# E16-PDB-5-LOAD_1.net
KiCad netlist of a schematic drawn in Altium Designer
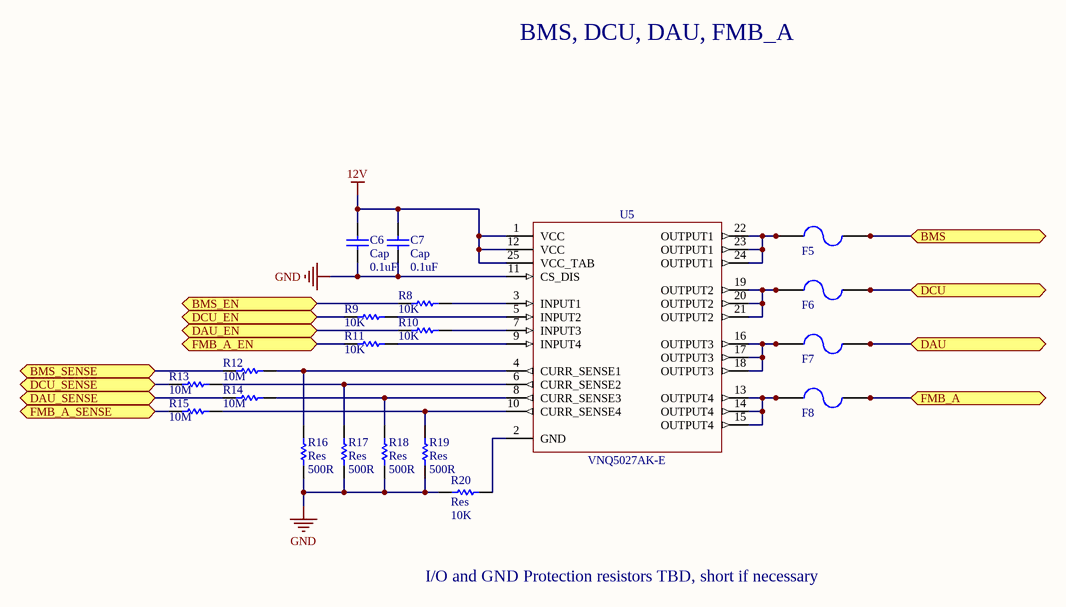
[diagram p0: E16-PDB-5-LOAD_1.SchDoc]

(export (version "E")
  (design (tool "Eeschema 10.0.6"))
  (components
    (comp (ref "C6")
      (value "Cap")
      (footprint "C0805")
      (description "Capacitor")
      (fields (field (name "ALTIUM_VALUE") "0.1uF") (field (name "PUBLISHER") "Altium Limited"))
      (libsource (lib "Capacitors") (part "Cap"))
    )
    (comp (ref "C7")
      (value "Cap")
      (footprint "C0805")
      (description "Capacitor")
      (fields (field (name "ALTIUM_VALUE") "0.1uF") (field (name "PUBLISHER") "Altium Limited"))
      (libsource (lib "Capacitors") (part "Cap"))
    )
    (comp (ref "F5")
      (value "BK-6013")
      (footprint "BK-6013")
      (description "FUSE HOLDER BLADE PCB")
      (libsource (lib "Fuses") (part "BK-6013"))
    )
    (comp (ref "F6")
      (value "BK-6013")
      (footprint "BK-6013")
      (description "FUSE HOLDER BLADE PCB")
      (libsource (lib "Fuses") (part "BK-6013"))
    )
    (comp (ref "F7")
      (value "BK-6013")
      (footprint "BK-6013")
      (description "FUSE HOLDER BLADE PCB")
      (libsource (lib "Fuses") (part "BK-6013"))
    )
    (comp (ref "F8")
      (value "BK-6013")
      (footprint "BK-6013")
      (description "FUSE HOLDER BLADE PCB")
      (libsource (lib "Fuses") (part "BK-6013"))
    )
    (comp (ref "R8")
      (value "10K")
      (footprint "2012[0805]")
      (description "Surface Mount Resistor")
      (fields (field (name "Comment") "Res") (field (name "PUBLISHER") "Altium Limited"))
      (libsource (lib "Resistors") (part "Res"))
    )
    (comp (ref "R9")
      (value "10K")
      (footprint "2012[0805]")
      (description "Surface Mount Resistor")
      (fields (field (name "Comment") "Res") (field (name "PUBLISHER") "Altium Limited"))
      (libsource (lib "Resistors") (part "Res"))
    )
    (comp (ref "R10")
      (value "10K")
      (footprint "2012[0805]")
      (description "Surface Mount Resistor")
      (fields (field (name "Comment") "Res") (field (name "PUBLISHER") "Altium Limited"))
      (libsource (lib "Resistors") (part "Res"))
    )
    (comp (ref "R11")
      (value "10K")
      (footprint "2012[0805]")
      (description "Surface Mount Resistor")
      (fields (field (name "Comment") "Res") (field (name "PUBLISHER") "Altium Limited"))
      (libsource (lib "Resistors") (part "Res"))
    )
    (comp (ref "R12")
      (value "10M")
      (footprint "2012[0805]")
      (description "Surface Mount Resistor")
      (fields (field (name "Comment") "Res") (field (name "PUBLISHER") "Altium Limited"))
      (libsource (lib "Resistors") (part "Res"))
    )
    (comp (ref "R13")
      (value "10M")
      (footprint "2012[0805]")
      (description "Surface Mount Resistor")
      (fields (field (name "Comment") "Res") (field (name "PUBLISHER") "Altium Limited"))
      (libsource (lib "Resistors") (part "Res"))
    )
    (comp (ref "R14")
      (value "10M")
      (footprint "2012[0805]")
      (description "Surface Mount Resistor")
      (fields (field (name "Comment") "Res") (field (name "PUBLISHER") "Altium Limited"))
      (libsource (lib "Resistors") (part "Res"))
    )
    (comp (ref "R15")
      (value "10M")
      (footprint "2012[0805]")
      (description "Surface Mount Resistor")
      (fields (field (name "Comment") "Res") (field (name "PUBLISHER") "Altium Limited"))
      (libsource (lib "Resistors") (part "Res"))
    )
    (comp (ref "R16")
      (value "Res")
      (footprint "2012[0805]")
      (description "Surface Mount Resistor")
      (fields (field (name "ALTIUM_VALUE") "500R") (field (name "PUBLISHER") "Altium Limited"))
      (libsource (lib "Resistors") (part "Res"))
    )
    (comp (ref "R17")
      (value "Res")
      (footprint "2012[0805]")
      (description "Surface Mount Resistor")
      (fields (field (name "ALTIUM_VALUE") "500R") (field (name "PUBLISHER") "Altium Limited"))
      (libsource (lib "Resistors") (part "Res"))
    )
    (comp (ref "R18")
      (value "Res")
      (footprint "2012[0805]")
      (description "Surface Mount Resistor")
      (fields (field (name "ALTIUM_VALUE") "500R") (field (name "PUBLISHER") "Altium Limited"))
      (libsource (lib "Resistors") (part "Res"))
    )
    (comp (ref "R19")
      (value "Res")
      (footprint "2012[0805]")
      (description "Surface Mount Resistor")
      (fields (field (name "ALTIUM_VALUE") "500R") (field (name "PUBLISHER") "Altium Limited"))
      (libsource (lib "Resistors") (part "Res"))
    )
    (comp (ref "R20")
      (value "Res")
      (footprint "2012[0805]")
      (description "Surface Mount Resistor")
      (fields (field (name "ALTIUM_VALUE") "10K") (field (name "PUBLISHER") "Altium Limited"))
      (libsource (lib "Resistors") (part "Res"))
    )
    (comp (ref "U5")
      (value "U_VNQ5027AK-E")
      (footprint "PowerSSO-24")
      (description "LOAD CHANNEL HIGH SIDE 42 A 4 Channel")
      (fields (field (name "MFG") "STmicroelectronics") (field (name "MFG_PN") "VNQ5027AK-E"))
      (libsource (lib "Transistors") (part "U_VNQ5027AK-E"))
    )
  )
  (nets
    (net (code "1") (name "/BMS") (class "Default")
      (node (ref "F5") (pin "3") (pinfunction "3_3") (pintype "passive"))
      (node (ref "F5") (pin "4") (pinfunction "4_4") (pintype "passive"))
    )
    (net (code "2") (name "/BMS_EN") (class "Default")
      (node (ref "R8") (pin "2") (pinfunction "2_2") (pintype "passive"))
    )
    (net (code "3") (name "/BMS_SENSE") (class "Default")
      (node (ref "R12") (pin "2") (pinfunction "2_2") (pintype "passive"))
    )
    (net (code "4") (name "/DAU") (class "Default")
      (node (ref "F7") (pin "3") (pinfunction "3_3") (pintype "passive"))
      (node (ref "F7") (pin "4") (pinfunction "4_4") (pintype "passive"))
    )
    (net (code "5") (name "/DAU_EN") (class "Default")
      (node (ref "R10") (pin "2") (pinfunction "2_2") (pintype "passive"))
    )
    (net (code "6") (name "/DAU_SENSE") (class "Default")
      (node (ref "R14") (pin "2") (pinfunction "2_2") (pintype "passive"))
    )
    (net (code "7") (name "/DCU") (class "Default")
      (node (ref "F6") (pin "3") (pinfunction "3_3") (pintype "passive"))
      (node (ref "F6") (pin "4") (pinfunction "4_4") (pintype "passive"))
    )
    (net (code "8") (name "/DCU_EN") (class "Default")
      (node (ref "R9") (pin "2") (pinfunction "2_2") (pintype "passive"))
    )
    (net (code "9") (name "/DCU_SENSE") (class "Default")
      (node (ref "R13") (pin "2") (pinfunction "2_2") (pintype "passive"))
    )
    (net (code "10") (name "/FMB_A") (class "Default")
      (node (ref "F8") (pin "3") (pinfunction "3_3") (pintype "passive"))
      (node (ref "F8") (pin "4") (pinfunction "4_4") (pintype "passive"))
    )
    (net (code "11") (name "/FMB_A_EN") (class "Default")
      (node (ref "R11") (pin "2") (pinfunction "2_2") (pintype "passive"))
    )
    (net (code "12") (name "/FMB_A_SENSE") (class "Default")
      (node (ref "R15") (pin "2") (pinfunction "2_2") (pintype "passive"))
    )
    (net (code "13") (name "12V") (class "Default")
      (node (ref "C6") (pin "2") (pinfunction "2_2") (pintype "passive"))
      (node (ref "C7") (pin "2") (pinfunction "2_2") (pintype "passive"))
      (node (ref "U5") (pin "1") (pinfunction "VCC_1") (pintype "power_in"))
      (node (ref "U5") (pin "12") (pinfunction "VCC_12") (pintype "power_in"))
      (node (ref "U5") (pin "25") (pinfunction "VCC_TAB_25") (pintype "power_in"))
    )
    (net (code "14") (name "GND") (class "Default")
      (node (ref "C6") (pin "1") (pinfunction "1_1") (pintype "passive"))
      (node (ref "C7") (pin "1") (pinfunction "1_1") (pintype "passive"))
      (node (ref "R16") (pin "1") (pinfunction "1_1") (pintype "passive"))
      (node (ref "R17") (pin "1") (pinfunction "1_1") (pintype "passive"))
      (node (ref "R18") (pin "1") (pinfunction "1_1") (pintype "passive"))
      (node (ref "R19") (pin "1") (pinfunction "1_1") (pintype "passive"))
      (node (ref "R20") (pin "2") (pinfunction "2_2") (pintype "passive"))
      (node (ref "U5") (pin "11") (pinfunction "CS_DIS_11") (pintype "input"))
    )
    (net (code "15") (name "Net-(F5-Pad1)") (class "Default")
      (node (ref "F5") (pin "1") (pinfunction "1_1") (pintype "passive"))
      (node (ref "F5") (pin "2") (pinfunction "2_2") (pintype "passive"))
      (node (ref "U5") (pin "22") (pinfunction "OUTPUT1_22") (pintype "output"))
      (node (ref "U5") (pin "23") (pinfunction "OUTPUT1_23") (pintype "output"))
      (node (ref "U5") (pin "24") (pinfunction "OUTPUT1_24") (pintype "output"))
    )
    (net (code "16") (name "Net-(F6-Pad1)") (class "Default")
      (node (ref "F6") (pin "1") (pinfunction "1_1") (pintype "passive"))
      (node (ref "F6") (pin "2") (pinfunction "2_2") (pintype "passive"))
      (node (ref "U5") (pin "19") (pinfunction "OUTPUT2_19") (pintype "output"))
      (node (ref "U5") (pin "20") (pinfunction "OUTPUT2_20") (pintype "output"))
      (node (ref "U5") (pin "21") (pinfunction "OUTPUT2_21") (pintype "output"))
    )
    (net (code "17") (name "Net-(F7-Pad1)") (class "Default")
      (node (ref "F7") (pin "1") (pinfunction "1_1") (pintype "passive"))
      (node (ref "F7") (pin "2") (pinfunction "2_2") (pintype "passive"))
      (node (ref "U5") (pin "16") (pinfunction "OUTPUT3_16") (pintype "output"))
      (node (ref "U5") (pin "17") (pinfunction "OUTPUT3_17") (pintype "output"))
      (node (ref "U5") (pin "18") (pinfunction "OUTPUT3_18") (pintype "output"))
    )
    (net (code "18") (name "Net-(F8-Pad1)") (class "Default")
      (node (ref "F8") (pin "1") (pinfunction "1_1") (pintype "passive"))
      (node (ref "F8") (pin "2") (pinfunction "2_2") (pintype "passive"))
      (node (ref "U5") (pin "13") (pinfunction "OUTPUT4_13") (pintype "output"))
      (node (ref "U5") (pin "14") (pinfunction "OUTPUT4_14") (pintype "output"))
      (node (ref "U5") (pin "15") (pinfunction "OUTPUT4_15") (pintype "output"))
    )
    (net (code "19") (name "Net-(U5-CURR_SENSE1)") (class "Default")
      (node (ref "R12") (pin "1") (pinfunction "1_1") (pintype "passive"))
      (node (ref "R16") (pin "2") (pinfunction "2_2") (pintype "passive"))
      (node (ref "U5") (pin "4") (pinfunction "CURR_SENSE1_4") (pintype "output"))
    )
    (net (code "20") (name "Net-(U5-CURR_SENSE2)") (class "Default")
      (node (ref "R13") (pin "1") (pinfunction "1_1") (pintype "passive"))
      (node (ref "R17") (pin "2") (pinfunction "2_2") (pintype "passive"))
      (node (ref "U5") (pin "6") (pinfunction "CURR_SENSE2_6") (pintype "output"))
    )
    (net (code "21") (name "Net-(U5-CURR_SENSE3)") (class "Default")
      (node (ref "R14") (pin "1") (pinfunction "1_1") (pintype "passive"))
      (node (ref "R18") (pin "2") (pinfunction "2_2") (pintype "passive"))
      (node (ref "U5") (pin "8") (pinfunction "CURR_SENSE3_8") (pintype "output"))
    )
    (net (code "22") (name "Net-(U5-CURR_SENSE4)") (class "Default")
      (node (ref "R15") (pin "1") (pinfunction "1_1") (pintype "passive"))
      (node (ref "R19") (pin "2") (pinfunction "2_2") (pintype "passive"))
      (node (ref "U5") (pin "10") (pinfunction "CURR_SENSE4_10") (pintype "output"))
    )
    (net (code "23") (name "Net-(U5-GND)") (class "Default")
      (node (ref "R20") (pin "1") (pinfunction "1_1") (pintype "passive"))
      (node (ref "U5") (pin "2") (pinfunction "GND_2") (pintype "power_in"))
    )
    (net (code "24") (name "Net-(U5-INPUT1)") (class "Default")
      (node (ref "R8") (pin "1") (pinfunction "1_1") (pintype "passive"))
      (node (ref "U5") (pin "3") (pinfunction "INPUT1_3") (pintype "input"))
    )
    (net (code "25") (name "Net-(U5-INPUT2)") (class "Default")
      (node (ref "R9") (pin "1") (pinfunction "1_1") (pintype "passive"))
      (node (ref "U5") (pin "5") (pinfunction "INPUT2_5") (pintype "input"))
    )
    (net (code "26") (name "Net-(U5-INPUT3)") (class "Default")
      (node (ref "R10") (pin "1") (pinfunction "1_1") (pintype "passive"))
      (node (ref "U5") (pin "7") (pinfunction "INPUT3_7") (pintype "input"))
    )
    (net (code "27") (name "Net-(U5-INPUT4)") (class "Default")
      (node (ref "R11") (pin "1") (pinfunction "1_1") (pintype "passive"))
      (node (ref "U5") (pin "9") (pinfunction "INPUT4_9") (pintype "input"))
    )
  )
)
